# Sheet1.net
KiCad netlist of a schematic drawn in Altium Designer
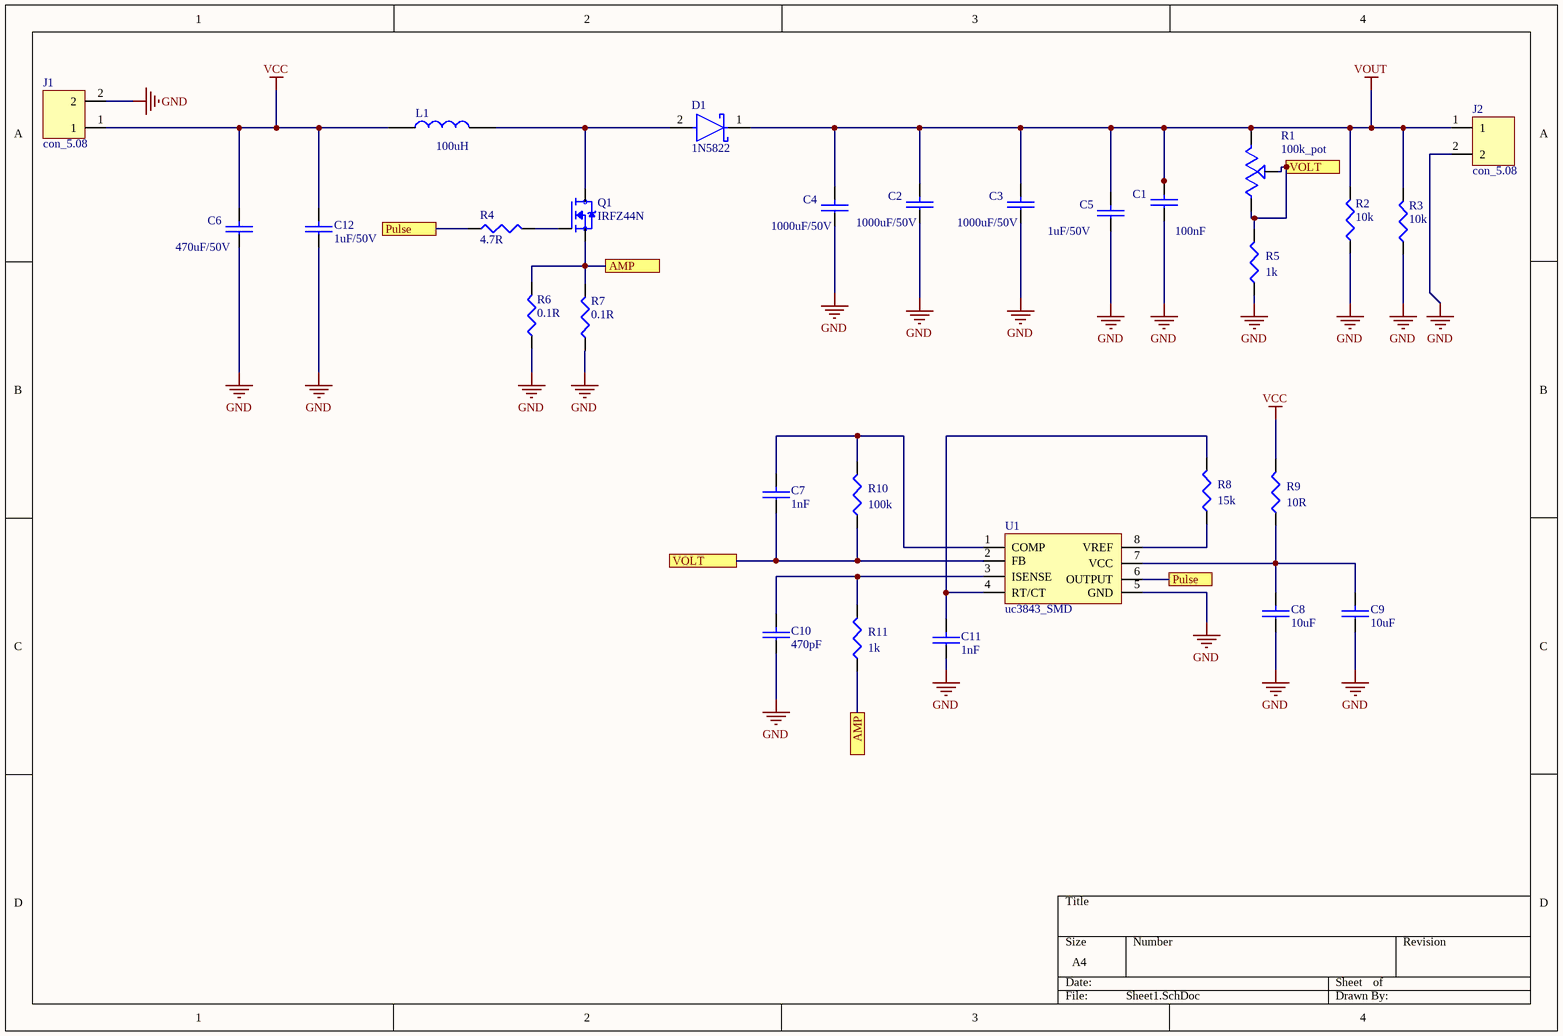
[diagram p0: Sheet1.SchDoc]

(export (version "E")
  (design (tool "Eeschema 10.0.6"))
  (components
    (comp (ref "C1") (value "100nF") (footprint "C1206_2uF") (libsource (lib "lib") (part "C1206_2uf")))
    (comp (ref "C2") (value "1000uF/50V") (footprint "C1206_2uF") (libsource (lib "lib") (part "C1206_2uf")))
    (comp (ref "C3") (value "1000uF/50V") (footprint "C1206_2uF") (libsource (lib "lib") (part "C1206_2uf")))
    (comp (ref "C4") (value "1000uF/50V") (footprint "C1206_2uF") (libsource (lib "lib") (part "C1206_2uf")))
    (comp (ref "C5") (value "1uF/50V") (footprint "C1206_2uF") (libsource (lib "lib") (part "C1206_2uf")))
    (comp (ref "C6") (value "470uF/50V") (footprint "C1206_2uF") (libsource (lib "lib") (part "C1206_2uf")))
    (comp (ref "C7") (value "1nF") (footprint "C1206_2uF") (libsource (lib "lib") (part "C1206_2uf")))
    (comp (ref "C8") (value "10uF") (footprint "C1206_2uF") (libsource (lib "lib") (part "C1206_2uf")))
    (comp (ref "C9") (value "10uF") (footprint "C1206_2uF") (libsource (lib "lib") (part "C1206_2uf")))
    (comp (ref "C10") (value "470pF") (footprint "C1206_2uF") (libsource (lib "lib") (part "C1206_2uf")))
    (comp (ref "C11") (value "1nF") (footprint "C1206_2uF") (libsource (lib "lib") (part "C1206_2uf")))
    (comp (ref "C12") (value "1uF/50V") (footprint "C1206_2uF") (libsource (lib "lib") (part "C1206_2uf")))
    (comp (ref "D1")
      (value "1N5822")
      (footprint "15SQ045")
      (libsource (lib "Main_Schematic_Library") (part "1N5822"))
    )
    (comp (ref "J1") (value "con_5.08") (footprint "5.08_con_1") (libsource (lib "") (part "con_5.08_1")))
    (comp (ref "J2") (value "con_5.08") (footprint "5.08_con_1") (libsource (lib "lib") (part "con_5.08")))
    (comp (ref "L1")
      (value "100uH")
      (footprint "100uH_SMD")
      (libsource (lib "Main_Schematic_Library") (part "100uH"))
    )
    (comp (ref "Q1")
      (value "IRFZ44N")
      (footprint "IRFZ44N")
      (description "N-Channel 55 V 49A (Tc) 94W (Tc) Through Hole TO-220AB")
      (libsource (lib "Main_Schematic_Library") (part "IRFZ44N"))
    )
    (comp (ref "R1") (value "100k_pot") (footprint "pot_100k_1") (libsource (lib "lib") (part "100k_pot")))
    (comp (ref "R2") (value "10k") (footprint "R2512") (libsource (lib "lib") (part "R2512_1W")))
    (comp (ref "R3") (value "10k") (footprint "R2512") (libsource (lib "lib") (part "R2512_1W")))
    (comp (ref "R4") (value "4.7R") (footprint "1206_Res") (libsource (lib "lib") (part "1206")))
    (comp (ref "R5") (value "1k") (footprint "1206_Res") (libsource (lib "lib") (part "1206")))
    (comp (ref "R6") (value "0.1R") (footprint "2512") (libsource (lib "lib") (part "2512")))
    (comp (ref "R7") (value "0.1R") (footprint "2512") (libsource (lib "lib") (part "2512")))
    (comp (ref "R8") (value "15k") (footprint "1206_Res") (libsource (lib "lib") (part "1206")))
    (comp (ref "R9") (value "10R") (footprint "1206_Res") (libsource (lib "lib") (part "1206")))
    (comp (ref "R10") (value "100k") (footprint "1206_Res") (libsource (lib "lib") (part "1206")))
    (comp (ref "R11") (value "1k") (footprint "1206_Res") (libsource (lib "lib") (part "1206")))
    (comp (ref "U1")
      (value "uc3843_SMD")
      (footprint "uc3843_SOIC8")
      (libsource (lib "lib") (part "uc3843_SMD"))
    )
  )
  (nets
    (net (code "1") (name "/AMP") (class "Default")
      (node (ref "Q1") (pin "3") (pinfunction "S_3") (pintype "passive"))
      (node (ref "R11") (pin "1") (pinfunction "1_1") (pintype "passive"))
      (node (ref "R6") (pin "2") (pinfunction "2_2") (pintype "passive"))
      (node (ref "R7") (pin "2") (pinfunction "2_2") (pintype "passive"))
    )
    (net (code "2") (name "/Pulse") (class "Default")
      (node (ref "R4") (pin "1") (pinfunction "1_1") (pintype "passive"))
      (node (ref "U1") (pin "6") (pinfunction "OUTPUT_6") (pintype "passive"))
    )
    (net (code "3") (name "/VOLT") (class "Default")
      (node (ref "C7") (pin "1") (pinfunction "1_1") (pintype "passive"))
      (node (ref "R1") (pin "1") (pinfunction "A_1") (pintype "passive"))
      (node (ref "R1") (pin "2") (pinfunction "B_2") (pintype "passive"))
      (node (ref "R10") (pin "1") (pinfunction "1_1") (pintype "passive"))
      (node (ref "R5") (pin "2") (pinfunction "2_2") (pintype "passive"))
      (node (ref "U1") (pin "2") (pinfunction "FB_2") (pintype "passive"))
    )
    (net (code "4") (name "GND") (class "Default")
      (node (ref "C1") (pin "1") (pinfunction "1_1") (pintype "passive"))
      (node (ref "C10") (pin "1") (pinfunction "1_1") (pintype "passive"))
      (node (ref "C11") (pin "1") (pinfunction "1_1") (pintype "passive"))
      (node (ref "C12") (pin "1") (pinfunction "1_1") (pintype "passive"))
      (node (ref "C2") (pin "1") (pinfunction "1_1") (pintype "passive"))
      (node (ref "C3") (pin "1") (pinfunction "1_1") (pintype "passive"))
      (node (ref "C4") (pin "1") (pinfunction "1_1") (pintype "passive"))
      (node (ref "C5") (pin "1") (pinfunction "1_1") (pintype "passive"))
      (node (ref "C6") (pin "1") (pinfunction "1_1") (pintype "passive"))
      (node (ref "C8") (pin "1") (pinfunction "1_1") (pintype "passive"))
      (node (ref "C9") (pin "1") (pinfunction "1_1") (pintype "passive"))
      (node (ref "J1") (pin "2") (pinfunction "2_2") (pintype "passive"))
      (node (ref "J2") (pin "2") (pinfunction "2_2") (pintype "passive"))
      (node (ref "R2") (pin "1") (pinfunction "1_1") (pintype "passive"))
      (node (ref "R3") (pin "1") (pinfunction "1_1") (pintype "passive"))
      (node (ref "R5") (pin "1") (pinfunction "1_1") (pintype "passive"))
      (node (ref "R6") (pin "1") (pinfunction "1_1") (pintype "passive"))
      (node (ref "R7") (pin "1") (pinfunction "1_1") (pintype "passive"))
      (node (ref "U1") (pin "5") (pinfunction "GND_5") (pintype "passive"))
    )
    (net (code "5") (name "Net-(D1-A)") (class "Default")
      (node (ref "D1") (pin "2") (pinfunction "A_2") (pintype "passive"))
      (node (ref "L1") (pin "2") (pinfunction "2_2") (pintype "passive"))
      (node (ref "Q1") (pin "2") (pinfunction "D_2") (pintype "passive"))
    )
    (net (code "6") (name "Net-(Q1-G)") (class "Default")
      (node (ref "Q1") (pin "1") (pinfunction "G_1") (pintype "passive"))
      (node (ref "R4") (pin "2") (pinfunction "2_2") (pintype "passive"))
    )
    (net (code "7") (name "Net-(U1-COMP)") (class "Default")
      (node (ref "C7") (pin "2") (pinfunction "2_2") (pintype "passive"))
      (node (ref "R10") (pin "2") (pinfunction "2_2") (pintype "passive"))
      (node (ref "U1") (pin "1") (pinfunction "COMP_1") (pintype "passive"))
    )
    (net (code "8") (name "Net-(U1-ISENSE)") (class "Default")
      (node (ref "C10") (pin "2") (pinfunction "2_2") (pintype "passive"))
      (node (ref "R11") (pin "2") (pinfunction "2_2") (pintype "passive"))
      (node (ref "U1") (pin "3") (pinfunction "ISENSE_3") (pintype "passive"))
    )
    (net (code "9") (name "Net-(U1-RT{slash}CT)") (class "Default")
      (node (ref "C11") (pin "2") (pinfunction "2_2") (pintype "passive"))
      (node (ref "R8") (pin "2") (pinfunction "2_2") (pintype "passive"))
      (node (ref "U1") (pin "4") (pinfunction "RT/CT_4") (pintype "passive"))
    )
    (net (code "10") (name "Net-(U1-VCC)") (class "Default")
      (node (ref "C8") (pin "2") (pinfunction "2_2") (pintype "passive"))
      (node (ref "C9") (pin "2") (pinfunction "2_2") (pintype "passive"))
      (node (ref "R9") (pin "1") (pinfunction "1_1") (pintype "passive"))
      (node (ref "U1") (pin "7") (pinfunction "VCC_7") (pintype "passive"))
    )
    (net (code "11") (name "Net-(U1-VREF)") (class "Default")
      (node (ref "R8") (pin "1") (pinfunction "1_1") (pintype "passive"))
      (node (ref "U1") (pin "8") (pinfunction "VREF_8") (pintype "passive"))
    )
    (net (code "12") (name "VCC") (class "Default")
      (node (ref "C12") (pin "2") (pinfunction "2_2") (pintype "passive"))
      (node (ref "C6") (pin "2") (pinfunction "2_2") (pintype "passive"))
      (node (ref "J1") (pin "1") (pinfunction "1_1") (pintype "passive"))
      (node (ref "L1") (pin "1") (pinfunction "1_1") (pintype "passive"))
      (node (ref "R9") (pin "2") (pinfunction "2_2") (pintype "passive"))
    )
    (net (code "13") (name "VOUT") (class "Default")
      (node (ref "C1") (pin "2") (pinfunction "2_2") (pintype "passive"))
      (node (ref "C2") (pin "2") (pinfunction "2_2") (pintype "passive"))
      (node (ref "C3") (pin "2") (pinfunction "2_2") (pintype "passive"))
      (node (ref "C4") (pin "2") (pinfunction "2_2") (pintype "passive"))
      (node (ref "C5") (pin "2") (pinfunction "2_2") (pintype "passive"))
      (node (ref "D1") (pin "1") (pinfunction "K_1") (pintype "passive"))
      (node (ref "J2") (pin "1") (pinfunction "1_1") (pintype "passive"))
      (node (ref "R1") (pin "3") (pinfunction "C_3") (pintype "passive"))
      (node (ref "R2") (pin "2") (pinfunction "2_2") (pintype "passive"))
      (node (ref "R3") (pin "2") (pinfunction "2_2") (pintype "passive"))
    )
  )
)
